# Velotour_2022_V1_0.net
KiCad netlist of a schematic drawn in Altium Designer
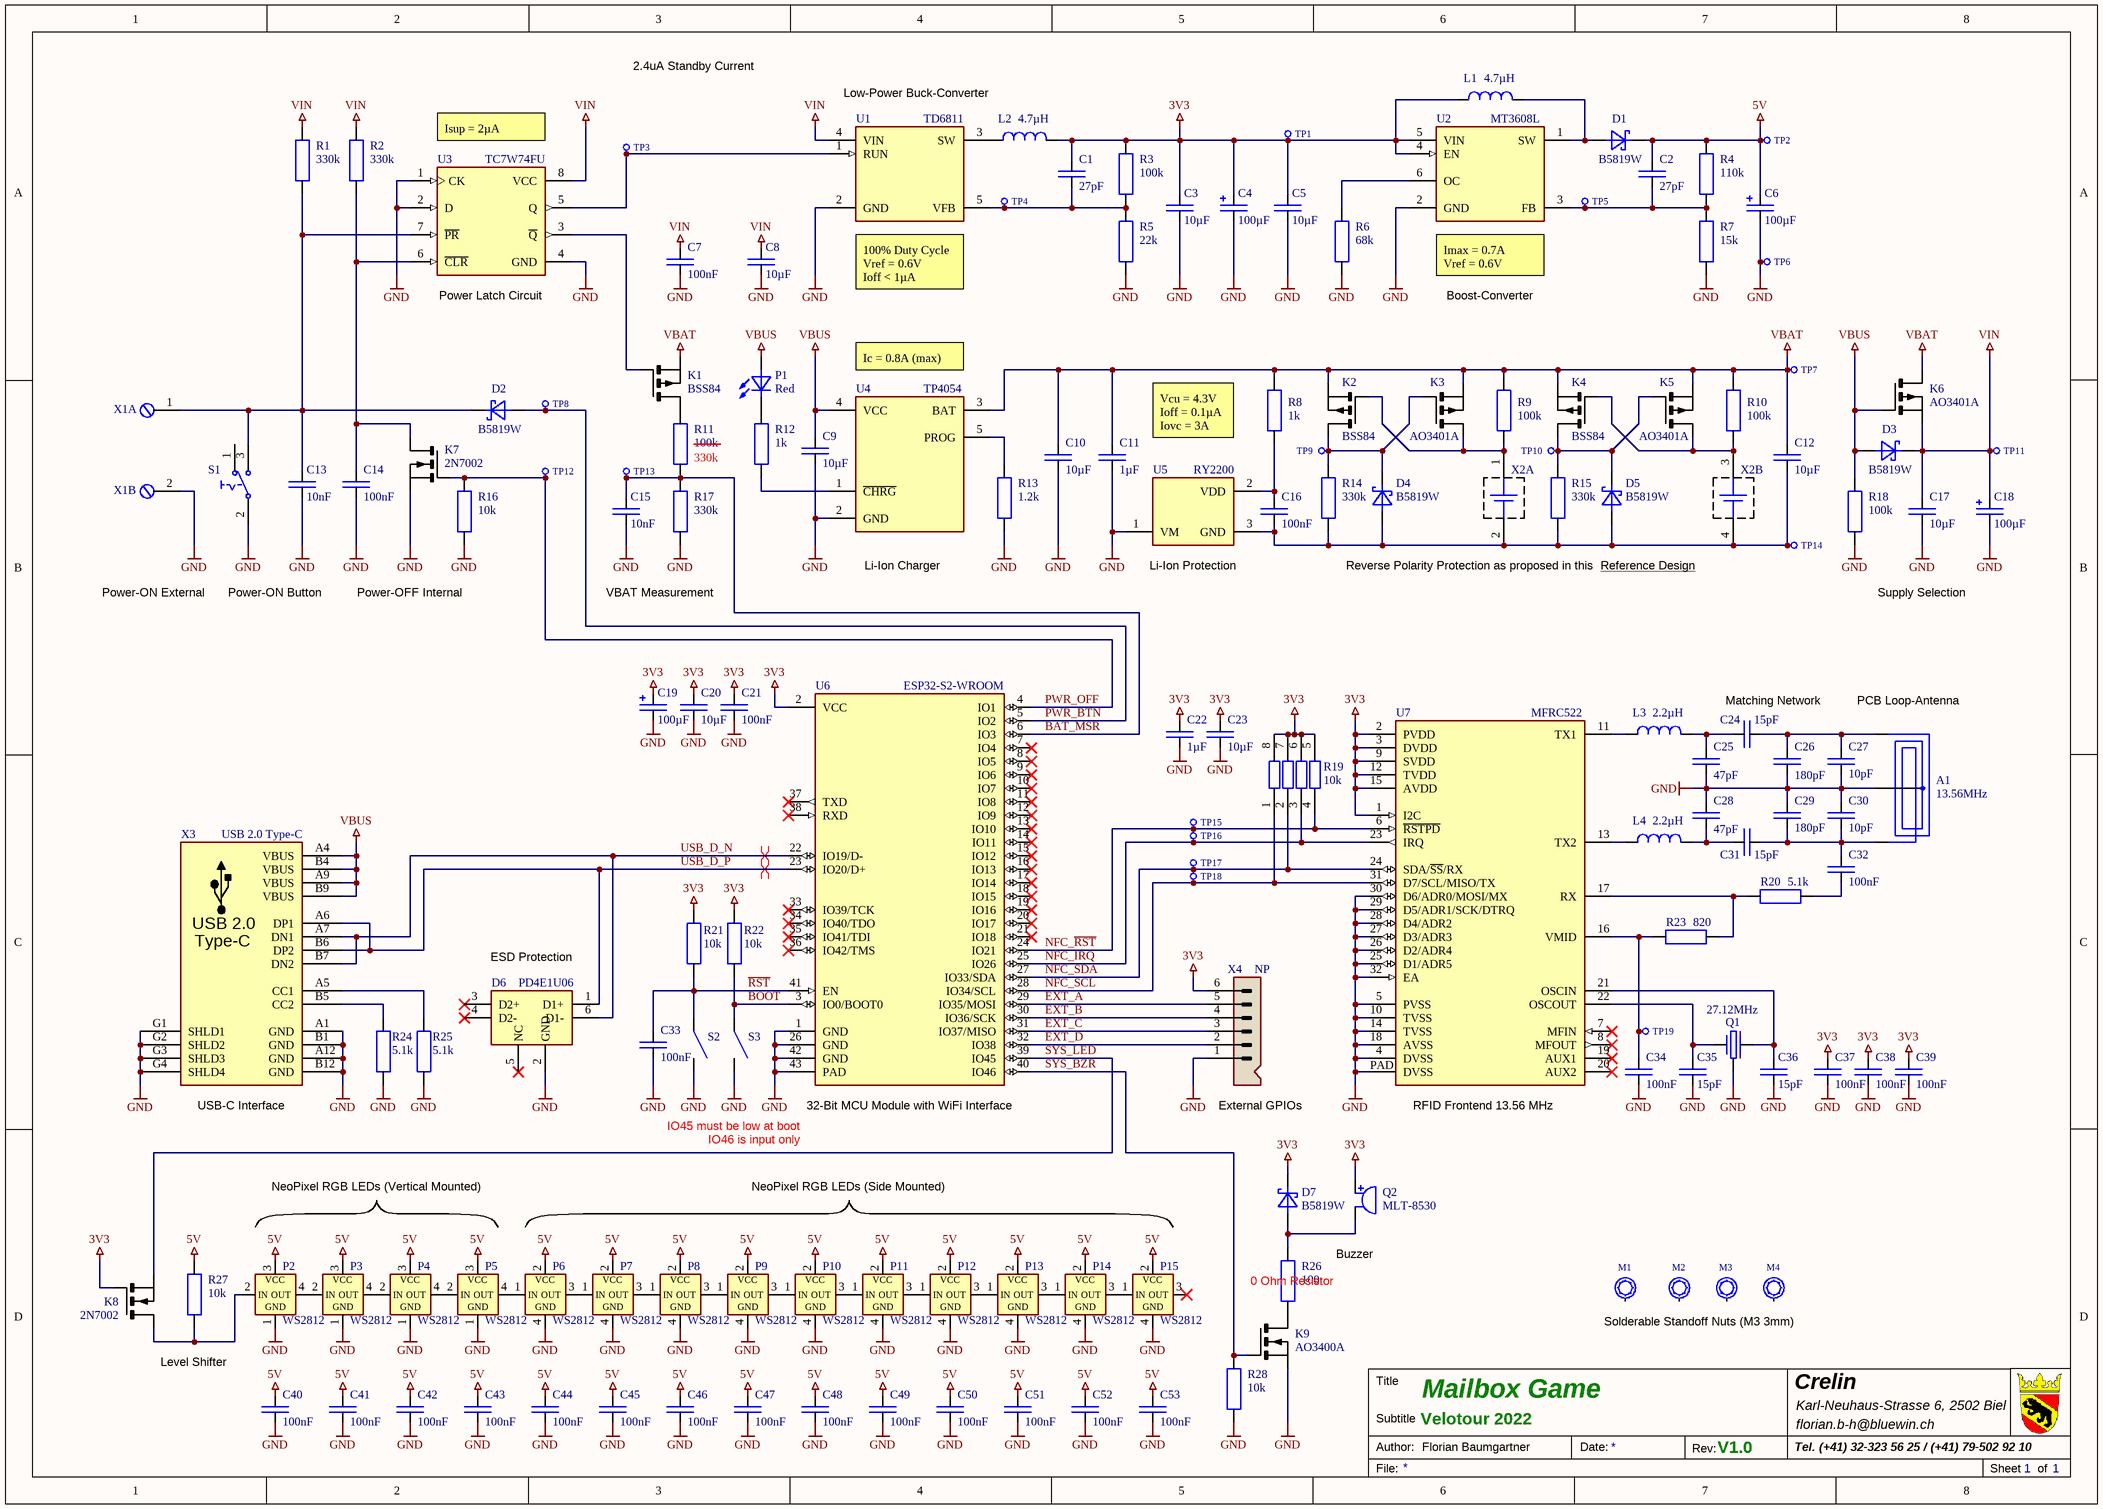
[diagram p0: Velotour_2022_V1.0.SchDoc]

(export (version "E")
  (design (tool "Eeschema 10.0.6"))
  (components
    (comp (ref "A1")
      (value "13.56MHz")
      (footprint "SMD Loop-Antenna 13.56MHz")
      (description "PCB Loop-Antenna")
      (libsource (lib "Velotour_2022") (part "A-Loop-Antenna"))
    )
    (comp (ref "C1")
      (value "27pF")
      (footprint "SMD Keramikkondensator 0603")
      (description "CAP-MK")
      (libsource (lib "AudioAmp") (part "C-CAPACITOR"))
    )
    (comp (ref "C2")
      (value "27pF")
      (footprint "SMD Keramikkondensator 0603")
      (description "CAP-MK")
      (libsource (lib "AudioAmp") (part "C-CAPACITOR"))
    )
    (comp (ref "C3")
      (value "10µF")
      (footprint "SMD Keramikkondensator 1206")
      (description "CAP-MK")
      (libsource (lib "AudioAmp") (part "C-CAPACITOR"))
    )
    (comp (ref "C4")
      (value "100µF")
      (footprint "SMD Tantalkondensator 1210 +")
      (description "CAP-Elko")
      (libsource (lib "TFS Integrated Library") (part "C-ELCAP"))
    )
    (comp (ref "C5")
      (value "10µF")
      (footprint "SMD Keramikkondensator 1206")
      (description "CAP-MK")
      (libsource (lib "AudioAmp") (part "C-CAPACITOR"))
    )
    (comp (ref "C6")
      (value "100µF")
      (footprint "SMD Tantalkondensator 1210 +")
      (description "CAP-Elko")
      (libsource (lib "TFS Integrated Library") (part "C-ELCAP"))
    )
    (comp (ref "C7")
      (value "100nF")
      (footprint "SMD Keramikkondensator 0603")
      (description "SMD Ceramic Capacitor E6")
      (libsource (lib "Ceramic Capacitors-E6") (part "E6 - 100nF"))
    )
    (comp (ref "C8")
      (value "10µF")
      (footprint "SMD Keramikkondensator 1206")
      (description "CAP-MK")
      (libsource (lib "AudioAmp") (part "C-CAPACITOR"))
    )
    (comp (ref "C9")
      (value "10µF")
      (footprint "SMD Keramikkondensator 1206")
      (description "SMD Ceramic Capacitor E6")
      (libsource (lib "Ceramic Capacitors-E6") (part "E6 - 10uF"))
    )
    (comp (ref "C10")
      (value "10µF")
      (footprint "SMD Keramikkondensator 1206")
      (description "SMD Ceramic Capacitor E6")
      (libsource (lib "Ceramic Capacitors-E6") (part "E6 - 10uF"))
    )
    (comp (ref "C11")
      (value "1µF")
      (footprint "SMD Keramikkondensator 0603")
      (description "CAP-MK")
      (libsource (lib "AudioAmp") (part "C-CAPACITOR"))
    )
    (comp (ref "C12")
      (value "10µF")
      (footprint "SMD Keramikkondensator 1206")
      (description "SMD Ceramic Capacitor E6")
      (libsource (lib "Ceramic Capacitors-E6") (part "E6 - 10uF"))
    )
    (comp (ref "C13")
      (value "10nF")
      (footprint "SMD Keramikkondensator 0603")
      (description "CAP-MK")
      (libsource (lib "AudioAmp") (part "C-CAPACITOR"))
    )
    (comp (ref "C14")
      (value "100nF")
      (footprint "SMD Keramikkondensator 0603")
      (description "SMD Ceramic Capacitor E6")
      (libsource (lib "Ceramic Capacitors-E6") (part "E6 - 100nF"))
    )
    (comp (ref "C15")
      (value "10nF")
      (footprint "SMD Keramikkondensator 0603")
      (description "CAP-MK")
      (libsource (lib "AudioAmp") (part "C-CAPACITOR"))
    )
    (comp (ref "C16")
      (value "100nF")
      (footprint "SMD Keramikkondensator 0603")
      (description "SMD Ceramic Capacitor E6")
      (libsource (lib "Ceramic Capacitors-E6") (part "E6 - 100nF"))
    )
    (comp (ref "C17")
      (value "10µF")
      (footprint "SMD Keramikkondensator 1206")
      (description "SMD Ceramic Capacitor E6")
      (libsource (lib "Ceramic Capacitors-E6") (part "E6 - 10uF"))
    )
    (comp (ref "C18")
      (value "100µF")
      (footprint "SMD Tantalkondensator 1210 +")
      (description "CAP-Elko")
      (libsource (lib "TFS Integrated Library") (part "C-ELCAP"))
    )
    (comp (ref "C19")
      (value "100µF")
      (footprint "SMD Tantalkondensator 1210 +")
      (description "CAP-Elko")
      (libsource (lib "TFS Integrated Library") (part "C-ELCAP"))
    )
    (comp (ref "C20")
      (value "10µF")
      (footprint "SMD Keramikkondensator 1206")
      (description "SMD Ceramic Capacitor E6")
      (libsource (lib "Ceramic Capacitors-E6") (part "E6 - 10uF"))
    )
    (comp (ref "C21")
      (value "100nF")
      (footprint "SMD Keramikkondensator 0603")
      (description "SMD Ceramic Capacitor E6")
      (libsource (lib "Ceramic Capacitors-E6") (part "E6 - 100nF"))
    )
    (comp (ref "C22")
      (value "1µF")
      (footprint "SMD Keramikkondensator 0603")
      (description "CAP-MK")
      (libsource (lib "AudioAmp") (part "C-CAPACITOR"))
    )
    (comp (ref "C23")
      (value "10µF")
      (footprint "SMD Keramikkondensator 1206")
      (description "SMD Ceramic Capacitor E6")
      (libsource (lib "Ceramic Capacitors-E6") (part "E6 - 10uF"))
    )
    (comp (ref "C24")
      (value "15pF")
      (footprint "SMD Keramikkondensator 0603")
      (description "CAP-MK")
      (libsource (lib "AudioAmp") (part "C-CAPACITOR"))
    )
    (comp (ref "C25")
      (value "47pF")
      (footprint "SMD Keramikkondensator 0603")
      (description "CAP-MK")
      (libsource (lib "AudioAmp") (part "C-CAPACITOR"))
    )
    (comp (ref "C26")
      (value "180pF")
      (footprint "SMD Keramikkondensator 0603")
      (description "CAP-MK")
      (libsource (lib "AudioAmp") (part "C-CAPACITOR"))
    )
    (comp (ref "C27")
      (value "10pF")
      (footprint "SMD Keramikkondensator 0603")
      (description "CAP-MK")
      (libsource (lib "AudioAmp") (part "C-CAPACITOR"))
    )
    (comp (ref "C28")
      (value "47pF")
      (footprint "SMD Keramikkondensator 0603")
      (description "CAP-MK")
      (libsource (lib "AudioAmp") (part "C-CAPACITOR"))
    )
    (comp (ref "C29")
      (value "180pF")
      (footprint "SMD Keramikkondensator 0603")
      (description "CAP-MK")
      (libsource (lib "AudioAmp") (part "C-CAPACITOR"))
    )
    (comp (ref "C30")
      (value "10pF")
      (footprint "SMD Keramikkondensator 0603")
      (description "CAP-MK")
      (libsource (lib "AudioAmp") (part "C-CAPACITOR"))
    )
    (comp (ref "C31")
      (value "15pF")
      (footprint "SMD Keramikkondensator 0603")
      (description "CAP-MK")
      (libsource (lib "AudioAmp") (part "C-CAPACITOR"))
    )
    (comp (ref "C32")
      (value "100nF")
      (footprint "SMD Keramikkondensator 0603")
      (description "SMD Ceramic Capacitor E6")
      (libsource (lib "Ceramic Capacitors-E6") (part "E6 - 100nF"))
    )
    (comp (ref "C33")
      (value "100nF")
      (footprint "SMD Keramikkondensator 0603")
      (description "SMD Ceramic Capacitor E6")
      (libsource (lib "Ceramic Capacitors-E6") (part "E6 - 100nF"))
    )
    (comp (ref "C34")
      (value "100nF")
      (footprint "SMD Keramikkondensator 0603")
      (description "SMD Ceramic Capacitor E6")
      (libsource (lib "Ceramic Capacitors-E6") (part "E6 - 100nF"))
    )
    (comp (ref "C35")
      (value "15pF")
      (footprint "SMD Keramikkondensator 0603")
      (description "CAP-MK")
      (libsource (lib "AudioAmp") (part "C-CAPACITOR"))
    )
    (comp (ref "C36")
      (value "15pF")
      (footprint "SMD Keramikkondensator 0603")
      (description "CAP-MK")
      (libsource (lib "AudioAmp") (part "C-CAPACITOR"))
    )
    (comp (ref "C37")
      (value "100nF")
      (footprint "SMD Keramikkondensator 0603")
      (description "SMD Ceramic Capacitor E6")
      (libsource (lib "Ceramic Capacitors-E6") (part "E6 - 100nF"))
    )
    (comp (ref "C38")
      (value "100nF")
      (footprint "SMD Keramikkondensator 0603")
      (description "SMD Ceramic Capacitor E6")
      (libsource (lib "Ceramic Capacitors-E6") (part "E6 - 100nF"))
    )
    (comp (ref "C39")
      (value "100nF")
      (footprint "SMD Keramikkondensator 0603")
      (description "SMD Ceramic Capacitor E6")
      (libsource (lib "Ceramic Capacitors-E6") (part "E6 - 100nF"))
    )
    (comp (ref "C40")
      (value "100nF")
      (footprint "SMD Keramikkondensator 0603")
      (description "SMD Ceramic Capacitor E6")
      (libsource (lib "Ceramic Capacitors-E6") (part "E6 - 100nF"))
    )
    (comp (ref "C41")
      (value "100nF")
      (footprint "SMD Keramikkondensator 0603")
      (description "SMD Ceramic Capacitor E6")
      (libsource (lib "Ceramic Capacitors-E6") (part "E6 - 100nF"))
    )
    (comp (ref "C42")
      (value "100nF")
      (footprint "SMD Keramikkondensator 0603")
      (description "SMD Ceramic Capacitor E6")
      (libsource (lib "Ceramic Capacitors-E6") (part "E6 - 100nF"))
    )
    (comp (ref "C43")
      (value "100nF")
      (footprint "SMD Keramikkondensator 0603")
      (description "SMD Ceramic Capacitor E6")
      (libsource (lib "Ceramic Capacitors-E6") (part "E6 - 100nF"))
    )
    (comp (ref "C44")
      (value "100nF")
      (footprint "SMD Keramikkondensator 0603")
      (description "SMD Ceramic Capacitor E6")
      (libsource (lib "Ceramic Capacitors-E6") (part "E6 - 100nF"))
    )
    (comp (ref "C45")
      (value "100nF")
      (footprint "SMD Keramikkondensator 0603")
      (description "SMD Ceramic Capacitor E6")
      (libsource (lib "Ceramic Capacitors-E6") (part "E6 - 100nF"))
    )
    (comp (ref "C46")
      (value "100nF")
      (footprint "SMD Keramikkondensator 0603")
      (description "SMD Ceramic Capacitor E6")
      (libsource (lib "Ceramic Capacitors-E6") (part "E6 - 100nF"))
    )
    (comp (ref "C47")
      (value "100nF")
      (footprint "SMD Keramikkondensator 0603")
      (description "SMD Ceramic Capacitor E6")
      (libsource (lib "Ceramic Capacitors-E6") (part "E6 - 100nF"))
    )
    (comp (ref "C48")
      (value "100nF")
      (footprint "SMD Keramikkondensator 0603")
      (description "SMD Ceramic Capacitor E6")
      (libsource (lib "Ceramic Capacitors-E6") (part "E6 - 100nF"))
    )
    (comp (ref "C49")
      (value "100nF")
      (footprint "SMD Keramikkondensator 0603")
      (description "SMD Ceramic Capacitor E6")
      (libsource (lib "Ceramic Capacitors-E6") (part "E6 - 100nF"))
    )
    (comp (ref "C50")
      (value "100nF")
      (footprint "SMD Keramikkondensator 0603")
      (description "SMD Ceramic Capacitor E6")
      (libsource (lib "Ceramic Capacitors-E6") (part "E6 - 100nF"))
    )
    (comp (ref "C51")
      (value "100nF")
      (footprint "SMD Keramikkondensator 0603")
      (description "SMD Ceramic Capacitor E6")
      (libsource (lib "Ceramic Capacitors-E6") (part "E6 - 100nF"))
    )
    (comp (ref "C52")
      (value "100nF")
      (footprint "SMD Keramikkondensator 0603")
      (description "SMD Ceramic Capacitor E6")
      (libsource (lib "Ceramic Capacitors-E6") (part "E6 - 100nF"))
    )
    (comp (ref "C53")
      (value "100nF")
      (footprint "SMD Keramikkondensator 0603")
      (description "SMD Ceramic Capacitor E6")
      (libsource (lib "Ceramic Capacitors-E6") (part "E6 - 100nF"))
    )
    (comp (ref "D1")
      (value "B5819W")
      (footprint "SMD Diode SOD-123")
      (description "S-DIODE")
      (libsource (lib "TFS Integrated Library") (part "R-DIODE{colon}SCHKY"))
    )
    (comp (ref "D2")
      (value "B5819W")
      (footprint "SMD Diode SOD-123")
      (description "S-DIODE")
      (libsource (lib "TFS Integrated Library") (part "R-DIODE{colon}SCHKY"))
    )
    (comp (ref "D3")
      (value "B5819W")
      (footprint "SMD Diode SOD-123")
      (description "S-DIODE")
      (libsource (lib "TFS Integrated Library") (part "R-DIODE{colon}SCHKY"))
    )
    (comp (ref "D4")
      (value "B5819W")
      (footprint "SMD Diode SOD-123")
      (description "S-DIODE")
      (libsource (lib "TFS Integrated Library") (part "R-DIODE{colon}SCHKY"))
    )
    (comp (ref "D5")
      (value "B5819W")
      (footprint "SMD Diode SOD-123")
      (description "S-DIODE")
      (libsource (lib "TFS Integrated Library") (part "R-DIODE{colon}SCHKY"))
    )
    (comp (ref "D6")
      (value "PD4E1U06")
      (footprint "SMD IC SOT-363 (SC-70-6)")
      (description "Unidirectional 3A (8/20us) 15V (Typ) 6.5V 5.5V (Max) SOT-363 ESD Protection Devices ROHS")
      (libsource (lib "Fleet-Monitor") (part "PD4E1U06DCKR"))
    )
    (comp (ref "D7")
      (value "B5819W")
      (footprint "SMD Diode SOD-123")
      (description "S-DIODE")
      (libsource (lib "TFS Integrated Library") (part "R-DIODE{colon}SCHKY"))
    )
    (comp (ref "K1")
      (value "BSS84")
      (footprint "SMD MOSFET SOT-23")
      (description "MOSFET P-Channel")
      (libsource (lib "VLD-Monitor_V1.0") (part "K-FET{colon}PIGE"))
    )
    (comp (ref "K2")
      (value "BSS84")
      (footprint "SMD MOSFET SOT-23")
      (description "MOSFET P-Channel")
      (libsource (lib "") (part "K-FET{colon}PIGE_2"))
    )
    (comp (ref "K3")
      (value "AO3401A")
      (footprint "SMD MOSFET SOT-23")
      (description "MOSFET P-Channel")
      (libsource (lib "VLD-Monitor_V1.0") (part "K-FET{colon}PIGE"))
    )
    (comp (ref "K4")
      (value "BSS84")
      (footprint "SMD MOSFET SOT-23")
      (description "MOSFET P-Channel")
      (libsource (lib "") (part "K-FET{colon}PIGE_2"))
    )
    (comp (ref "K5")
      (value "AO3401A")
      (footprint "SMD MOSFET SOT-23")
      (description "MOSFET P-Channel")
      (libsource (lib "VLD-Monitor_V1.0") (part "K-FET{colon}PIGE"))
    )
    (comp (ref "K6")
      (value "AO3401A")
      (footprint "SMD MOSFET SOT-23")
      (description "MOSFET P-Channel")
      (libsource (lib "") (part "K-FET{colon}PIGE_1"))
    )
    (comp (ref "K7")
      (value "2N7002")
      (footprint "SMD MOSFET SOT-23")
      (description "MOSFET N-Channel")
      (libsource (lib "") (part "K-FET{colon}NIGE_2"))
    )
    (comp (ref "K8")
      (value "2N7002")
      (footprint "SMD MOSFET SOT-23")
      (description "MOSFET N-Channel")
      (libsource (lib "Nixie-Test") (part "K-FET{colon}NIGE"))
    )
    (comp (ref "K9")
      (value "AO3400A")
      (footprint "SMD MOSFET SOT-23")
      (description "MOSFET N-Channel")
      (libsource (lib "") (part "K-FET{colon}NIGE_1"))
    )
    (comp (ref "L1")
      (value "4.7µH")
      (footprint "SMD Inductor 3.2x2.5x1.7")
      (description "Shielded Power Inductor")
      (libsource (lib "Nixie-Test") (part "L-COIL"))
    )
    (comp (ref "L2")
      (value "4.7µH")
      (footprint "SMD Inductor 3.2x2.5x1.7")
      (description "Shielded Power Inductor")
      (libsource (lib "Nixie-Test") (part "L-COIL"))
    )
    (comp (ref "L3")
      (value "2.2µH")
      (footprint "SMD Inductor 0805")
      (description "Multilayer Chip Inductor")
      (libsource (lib "Nixie-Test") (part "L-COIL"))
    )
    (comp (ref "L4")
      (value "2.2µH")
      (footprint "SMD Inductor 0805")
      (description "Multilayer Chip Inductor")
      (libsource (lib "Nixie-Test") (part "L-COIL"))
    )
    (comp (ref "M1")
      (value "SMTSO-M3-3ET")
      (footprint "SMD Solder-Nut (M3 3mm)")
      (description "Solderable Standoff Nut")
      (libsource (lib "Velotour_2022") (part "M-Spacer_M3_3mm"))
    )
    (comp (ref "M2")
      (value "SMTSO-M3-3ET")
      (footprint "SMD Solder-Nut (M3 3mm)")
      (description "Solderable Standoff Nut")
      (libsource (lib "Velotour_2022") (part "M-Spacer_M3_3mm"))
    )
    (comp (ref "M3")
      (value "SMTSO-M3-3ET")
      (footprint "SMD Solder-Nut (M3 3mm)")
      (description "Solderable Standoff Nut")
      (libsource (lib "Velotour_2022") (part "M-Spacer_M3_3mm"))
    )
    (comp (ref "M4")
      (value "SMTSO-M3-3ET")
      (footprint "SMD Solder-Nut (M3 3mm)")
      (description "Solderable Standoff Nut")
      (libsource (lib "Velotour_2022") (part "M-Spacer_M3_3mm"))
    )
    (comp (ref "P1")
      (value "Red")
      (footprint "SMD LED 0603")
      (description "LED (als Lampe E / alt H)")
      (libsource (lib "TFS Integrated Library") (part "P-LED"))
    )
    (comp (ref "P2")
      (value "WS2812")
      (footprint "SMD LED WS2812B-3528")
      (description "Smart RGB-LED")
      (libsource (lib "Velotour_2022") (part "P-WS2812B-3528"))
    )
    (comp (ref "P3")
      (value "WS2812")
      (footprint "SMD LED WS2812B-3528")
      (description "Smart RGB-LED")
      (libsource (lib "Velotour_2022") (part "P-WS2812B-3528"))
    )
    (comp (ref "P4")
      (value "WS2812")
      (footprint "SMD LED WS2812B-3528")
      (description "Smart RGB-LED")
      (libsource (lib "Velotour_2022") (part "P-WS2812B-3528"))
    )
    (comp (ref "P5")
      (value "WS2812")
      (footprint "SMD LED WS2812B-3528")
      (description "Smart RGB-LED")
      (libsource (lib "Velotour_2022") (part "P-WS2812B-3528"))
    )
    (comp (ref "P6")
      (value "WS2812")
      (footprint "SMD LED WS2812B-4020")
      (description "Smart RGB-LED")
      (libsource (lib "Velotour_2022") (part "P-WS2812B-4020"))
    )
    (comp (ref "P7")
      (value "WS2812")
      (footprint "SMD LED WS2812B-4020")
      (description "Smart RGB-LED")
      (libsource (lib "Velotour_2022") (part "P-WS2812B-4020"))
    )
    (comp (ref "P8")
      (value "WS2812")
      (footprint "SMD LED WS2812B-4020")
      (description "Smart RGB-LED")
      (libsource (lib "Velotour_2022") (part "P-WS2812B-4020"))
    )
    (comp (ref "P9")
      (value "WS2812")
      (footprint "SMD LED WS2812B-4020")
      (description "Smart RGB-LED")
      (libsource (lib "Velotour_2022") (part "P-WS2812B-4020"))
    )
    (comp (ref "P10")
      (value "WS2812")
      (footprint "SMD LED WS2812B-4020")
      (description "Smart RGB-LED")
      (libsource (lib "Velotour_2022") (part "P-WS2812B-4020"))
    )
    (comp (ref "P11")
      (value "WS2812")
      (footprint "SMD LED WS2812B-4020")
      (description "Smart RGB-LED")
      (libsource (lib "Velotour_2022") (part "P-WS2812B-4020"))
    )
    (comp (ref "P12")
      (value "WS2812")
      (footprint "SMD LED WS2812B-4020")
      (description "Smart RGB-LED")
      (libsource (lib "Velotour_2022") (part "P-WS2812B-4020"))
    )
    (comp (ref "P13")
      (value "WS2812")
      (footprint "SMD LED WS2812B-4020")
      (description "Smart RGB-LED")
      (libsource (lib "Velotour_2022") (part "P-WS2812B-4020"))
    )
    (comp (ref "P14")
      (value "WS2812")
      (footprint "SMD LED WS2812B-4020")
      (description "Smart RGB-LED")
      (libsource (lib "Velotour_2022") (part "P-WS2812B-4020"))
    )
    (comp (ref "P15")
      (value "WS2812")
      (footprint "SMD LED WS2812B-4020")
      (description "Smart RGB-LED")
      (libsource (lib "Velotour_2022") (part "P-WS2812B-4020"))
    )
    (comp (ref "Q1")
      (value "27.12MHz")
      (footprint "SMD Crystal 3.2X2.5X0.8")
      (libsource (lib "LED-Ring") (part "B-QUARZ-CAP"))
    )
    (comp (ref "Q2")
      (value "MLT-8530")
      (footprint "SMD Buzzer (MLT-8530)")
      (description "Electromagnetic Buzzer")
      (libsource (lib "Velotour_2022") (part "Q-Buzzer"))
    )
    (comp (ref "R1")
      (value "330k")
      (footprint "SMD Widerstand 0603")
      (description "RES (E=Heizwiderstand B=Messwandler)")
      (libsource (lib "") (part "R-RESISTOR_2"))
    )
    (comp (ref "R2")
      (value "330k")
      (footprint "SMD Widerstand 0603")
      (description "RES (E=Heizwiderstand B=Messwandler)")
      (libsource (lib "") (part "R-RESISTOR_2"))
    )
    (comp (ref "R3")
      (value "100k")
      (footprint "SMD Widerstand 0603")
      (description "RES (E=Heizwiderstand B=Messwandler)")
      (libsource (lib "") (part "R-RESISTOR_2"))
    )
    (comp (ref "R4")
      (value "110k")
      (footprint "SMD Widerstand 0603")
      (description "RES (E=Heizwiderstand B=Messwandler)")
      (libsource (lib "") (part "R-RESISTOR_2"))
    )
    (comp (ref "R5")
      (value "22k")
      (footprint "SMD Widerstand 0603")
      (description "RES (E=Heizwiderstand B=Messwandler)")
      (libsource (lib "TFS Integrated Library") (part "R-RESISTOR"))
    )
    (comp (ref "R6")
      (value "68k")
      (footprint "SMD Widerstand 0603")
      (description "RES (E=Heizwiderstand B=Messwandler)")
      (libsource (lib "") (part "R-RESISTOR_1"))
    )
    (comp (ref "R7")
      (value "15k")
      (footprint "SMD Widerstand 0603")
      (description "RES (E=Heizwiderstand B=Messwandler)")
      (libsource (lib "") (part "R-RESISTOR_2"))
    )
    (comp (ref "R8")
      (value "1k")
      (footprint "SMD Widerstand 0603")
      (description "RES (E=Heizwiderstand B=Messwandler)")
      (libsource (lib "TFS Integrated Library") (part "R-RESISTOR"))
    )
    (comp (ref "R9")
      (value "100k")
      (footprint "SMD Widerstand 0603")
      (description "RES (E=Heizwiderstand B=Messwandler)")
      (libsource (lib "") (part "R-RESISTOR_2"))
    )
    (comp (ref "R10")
      (value "100k")
      (footprint "SMD Widerstand 0603")
      (description "RES (E=Heizwiderstand B=Messwandler)")
      (libsource (lib "") (part "R-RESISTOR_2"))
    )
    (comp (ref "R11")
      (value "100k")
      (footprint "SMD Widerstand 0603")
      (description "RES (E=Heizwiderstand B=Messwandler)")
      (libsource (lib "") (part "R-RESISTOR_2"))
    )
    (comp (ref "R12")
      (value "1k")
      (footprint "SMD Widerstand 0603")
      (description "RES (E=Heizwiderstand B=Messwandler)")
      (libsource (lib "") (part "R-RESISTOR_3"))
    )
    (comp (ref "R13")
      (value "1.2k")
      (footprint "SMD Widerstand 0603")
      (description "RES (E=Heizwiderstand B=Messwandler)")
      (libsource (lib "") (part "R-RESISTOR_2"))
    )
    (comp (ref "R14")
      (value "330k")
      (footprint "SMD Widerstand 0603")
      (description "RES (E=Heizwiderstand B=Messwandler)")
      (libsource (lib "") (part "R-RESISTOR_2"))
    )
    (comp (ref "R15")
      (value "330k")
      (footprint "SMD Widerstand 0603")
      (description "RES (E=Heizwiderstand B=Messwandler)")
      (libsource (lib "") (part "R-RESISTOR_2"))
    )
    (comp (ref "R16")
      (value "10k")
      (footprint "SMD Widerstand 0603")
      (description "RES (E=Heizwiderstand B=Messwandler)")
      (libsource (lib "TFS Integrated Library") (part "R-RESISTOR"))
    )
    (comp (ref "R17")
      (value "330k")
      (footprint "SMD Widerstand 0603")
      (description "RES (E=Heizwiderstand B=Messwandler)")
      (libsource (lib "") (part "R-RESISTOR_2"))
    )
    (comp (ref "R18")
      (value "100k")
      (footprint "SMD Widerstand 0603")
      (description "RES (E=Heizwiderstand B=Messwandler)")
      (libsource (lib "") (part "R-RESISTOR_2"))
    )
    (comp (ref "R19")
      (value "10k")
      (footprint "SMD Widerstand Array 4-Fach 0603")
      (description "Isolated Resistor Array")
      (libsource (lib "Fleet-Monitor") (part "R-Array Single Quad E24 - 10k"))
    )
    (comp (ref "R20")
      (value "5.1k")
      (footprint "SMD Widerstand 0603")
      (description "RES (E=Heizwiderstand B=Messwandler)")
      (libsource (lib "") (part "R-RESISTOR_2"))
    )
    (comp (ref "R21")
      (value "10k")
      (footprint "SMD Widerstand 0603")
      (description "RES (E=Heizwiderstand B=Messwandler)")
      (libsource (lib "TFS Integrated Library") (part "R-RESISTOR"))
    )
    (comp (ref "R22")
      (value "10k")
      (footprint "SMD Widerstand 0603")
      (description "RES (E=Heizwiderstand B=Messwandler)")
      (libsource (lib "TFS Integrated Library") (part "R-RESISTOR"))
    )
    (comp (ref "R23")
      (value "820")
      (footprint "SMD Widerstand 0603")
      (description "SMD-Widerstand 1/4W")
      (libsource (lib "Backplane_1") (part "R-RESISTOR"))
    )
    (comp (ref "R24")
      (value "5.1k")
      (footprint "SMD Widerstand 0603")
      (description "RES (E=Heizwiderstand B=Messwandler)")
      (libsource (lib "") (part "R-RESISTOR_1"))
    )
    (comp (ref "R25")
      (value "5.1k")
      (footprint "SMD Widerstand 0603")
      (description "RES (E=Heizwiderstand B=Messwandler)")
      (libsource (lib "") (part "R-RESISTOR_1"))
    )
    (comp (ref "R26")
      (value "100")
      (footprint "SMD Widerstand 0603")
      (description "SMD-Widerstand 1/4W")
      (libsource (lib "") (part "R-RESISTOR_1"))
    )
    (comp (ref "R27")
      (value "10k")
      (footprint "SMD Widerstand 0603")
      (description "RES (E=Heizwiderstand B=Messwandler)")
      (libsource (lib "TFS Integrated Library") (part "R-RESISTOR"))
    )
    (comp (ref "R28")
      (value "10k")
      (footprint "SMD Widerstand 0603")
      (description "RES (E=Heizwiderstand B=Messwandler)")
      (libsource (lib "TFS Integrated Library") (part "R-RESISTOR"))
    )
    (comp (ref "S1")
      (value "SS075Q102F035V2A")
      (footprint "THT Micro Switch (SS075Q102F035V2A)")
      (description "Micro Detector Switch")
      (libsource (lib "Custom ST-Link") (part "S-PCM12SMTR"))
    )
    (comp (ref "S2")
      (value "SMD-Button")
      (footprint "SMD Button 5.2x5.2")
      (description "Button SPST")
      (libsource (lib "Switches") (part "Button 3mmx2.5mm"))
    )
    (comp (ref "S3")
      (value "SMD-Button")
      (footprint "SMD Button 5.2x5.2")
      (description "Button SPST")
      (libsource (lib "Switches") (part "Button 3mmx2.5mm"))
    )
    (comp (ref "TP1")
      (value "X-TP")
      (footprint "SMD Testpunkt Ø1mm")
      (description "Testpunkt")
      (libsource (lib "VLD-Monitor_V1.0") (part "X-TP"))
    )
    (comp (ref "TP2")
      (value "X-TP")
      (footprint "SMD Testpunkt Ø1mm")
      (description "Testpunkt")
      (libsource (lib "VLD-Monitor_V1.0") (part "X-TP"))
    )
    (comp (ref "TP3")
      (value "X-TP")
      (footprint "SMD Testpunkt Ø1mm")
      (description "Testpunkt")
      (libsource (lib "VLD-Monitor_V1.0") (part "X-TP"))
    )
    (comp (ref "TP4")
      (value "X-TP")
      (footprint "SMD Testpunkt Ø1mm")
      (description "Testpunkt")
      (libsource (lib "VLD-Monitor_V1.0") (part "X-TP"))
    )
    (comp (ref "TP5")
      (value "X-TP")
      (footprint "SMD Testpunkt Ø1mm")
      (description "Testpunkt")
      (libsource (lib "VLD-Monitor_V1.0") (part "X-TP"))
    )
    (comp (ref "TP6")
      (value "X-TP")
      (footprint "SMD Testpunkt Ø1mm")
      (description "Testpunkt")
      (libsource (lib "VLD-Monitor_V1.0") (part "X-TP"))
    )
    (comp (ref "TP7")
      (value "X-TP")
      (footprint "SMD Testpunkt Ø1mm")
      (description "Testpunkt")
      (libsource (lib "VLD-Monitor_V1.0") (part "X-TP"))
    )
    (comp (ref "TP8")
      (value "X-TP")
      (footprint "SMD Testpunkt Ø1mm")
      (description "Testpunkt")
      (libsource (lib "VLD-Monitor_V1.0") (part "X-TP"))
    )
    (comp (ref "TP9")
      (value "X-TP")
      (footprint "SMD Testpunkt Ø1mm")
      (description "Testpunkt")
      (libsource (lib "VLD-Monitor_V1.0") (part "X-TP"))
    )
    (comp (ref "TP10")
      (value "X-TP")
      (footprint "SMD Testpunkt Ø1mm")
      (description "Testpunkt")
      (libsource (lib "VLD-Monitor_V1.0") (part "X-TP"))
    )
    (comp (ref "TP11")
      (value "X-TP")
      (footprint "SMD Testpunkt Ø1mm")
      (description "Testpunkt")
      (libsource (lib "VLD-Monitor_V1.0") (part "X-TP"))
    )
    (comp (ref "TP12")
      (value "X-TP")
      (footprint "SMD Testpunkt Ø1mm")
      (description "Testpunkt")
      (libsource (lib "VLD-Monitor_V1.0") (part "X-TP"))
    )
    (comp (ref "TP13")
      (value "X-TP")
      (footprint "SMD Testpunkt Ø1mm")
      (description "Testpunkt")
      (libsource (lib "VLD-Monitor_V1.0") (part "X-TP"))
    )
    (comp (ref "TP14")
      (value "X-TP")
      (footprint "SMD Testpunkt Ø1mm")
      (description "Testpunkt")
      (libsource (lib "VLD-Monitor_V1.0") (part "X-TP"))
    )
    (comp (ref "TP15")
      (value "X-TP")
      (footprint "SMD Testpunkt Ø1mm")
      (description "Testpunkt")
      (libsource (lib "VLD-Monitor_V1.0") (part "X-TP"))
    )
    (comp (ref "TP16")
      (value "X-TP")
      (footprint "SMD Testpunkt Ø1mm")
      (description "Testpunkt")
      (libsource (lib "VLD-Monitor_V1.0") (part "X-TP"))
    )
    (comp (ref "TP17")
      (value "X-TP")
      (footprint "SMD Testpunkt Ø1mm")
      (description "Testpunkt")
      (libsource (lib "VLD-Monitor_V1.0") (part "X-TP"))
    )
    (comp (ref "TP18")
      (value "X-TP")
      (footprint "SMD Testpunkt Ø1mm")
      (description "Testpunkt")
      (libsource (lib "VLD-Monitor_V1.0") (part "X-TP"))
    )
    (comp (ref "TP19")
      (value "X-TP")
      (footprint "SMD Testpunkt Ø1mm")
      (description "Testpunkt")
      (libsource (lib "VLD-Monitor_V1.0") (part "X-TP"))
    )
    (comp (ref "U1")
      (value "TD6811")
      (footprint "SMD IC SOT-23-5")
      (description "1.5MHz 1.2A Synchronous Step-Down Converter")
      (libsource (lib "Velotour_2022") (part "U-TD6811"))
    )
    (comp (ref "U2")
      (value "MT3608L")
      (footprint "SMD IC SOT-23-6")
      (description "1.2MHz 2.5A Current Mode Step-Up Converter")
      (libsource (lib "Velotour_2022") (part "U-MT3608L"))
    )
    (comp (ref "U3")
      (value "TC7W74FU")
      (footprint "SMD IC TSSOP-8")
      (description "Low-Power D-Flip-Flop with Preset & Clear")
      (libsource (lib "Velotour_2022") (part "U-TC7W74FU"))
    )
    (comp (ref "U4")
      (value "TP4054")
      (footprint "SMD IC SOT-23-5")
      (description "Standalone Linear Li-Ion Battery Charger")
      (libsource (lib "Velotour_2022") (part "U-TP4054"))
    )
    (comp (ref "U5")
      (value "RY2200")
      (footprint "SMD IC SOT-23-3")
      (description "One Cell Li-ion and Li-poly Battery Protection IC")
      (libsource (lib "Velotour_2022") (part "U-RY2200"))
    )
    (comp (ref "U6")
      (value "ESP32-S2-WROOM")
      (footprint "SMD ESP32-S2-WROOM")
      (description "WiFi 802.11b/g/n Transceiver Module 2.4GHz Antenna, I-PEX Surface Mount")
      (libsource (lib "Fleet-Monitor") (part "ESP32-S2-WROOM"))
    )
    (comp (ref "U7")
      (value "MFRC522")
      (footprint "SMD IC QFN-32")
      (description "Standard performance MIFARE and NTAG frontend")
      (libsource (lib "Velotour_2022") (part "U-MFRC522"))
    )
    (comp (ref "X1")
      (value "X-Klemme (2-Pol)")
      (footprint "THT Schraubklemme 2-Pol (WJ500V-5.08-2P)")
      (libsource (lib "Quad-Current-Probe") (part "X-Klemme (2-Pol)"))
    )
    (comp (ref "X2")
      (value "18650 Dual Battery Holder")
      (footprint "SMD Battery-Holder (1048P)")
      (libsource (lib "Velotour_2022") (part "X-18650_Dual-Holder"))
    )
    (comp (ref "X3")
      (value "USB 2.0 Type-C")
      (footprint "THT USB-C Socket (KH-TYPE-C-L10-14P)")
      (description "Type-C")
      (libsource (lib "Velotour_2022") (part "X-USB-Buchse_Vertical"))
    )
    (comp (ref "X4")
      (value "NP")
      (footprint "THT Pin-Header 1x6 (NP)")
      (libsource (lib "Audio-Beamformer") (part "X-Stiftleiste (6-Fach)"))
    )
  )
  (nets
    (net (code "1") (name "/BAT_MSR") (class "Default")
      (node (ref "C15") (pin "2") (pinfunction "2_2") (pintype "passive"))
      (node (ref "R11") (pin "1") (pinfunction "1_1") (pintype "passive"))
      (node (ref "R17") (pin "2") (pinfunction "2_2") (pintype "passive"))
      (node (ref "TP13") (pin "1") (pinfunction "1_1") (pintype "passive"))
      (node (ref "U6") (pin "6") (pinfunction "IO3_6") (pintype "bidirectional"))
    )
    (net (code "2") (name "/BOOT") (class "Default")
      (node (ref "R22") (pin "1") (pinfunction "1_1") (pintype "passive"))
      (node (ref "S3") (pin "1") (pinfunction "1_1") (pintype "passive"))
      (node (ref "U6") (pin "3") (pinfunction "IO0/BOOT0_3") (pintype "bidirectional"))
    )
    (net (code "3") (name "/EXT_A") (class "Default")
      (node (ref "U6") (pin "29") (pinfunction "IO35/MOSI_29") (pintype "bidirectional"))
      (node (ref "X4") (pin "5") (pinfunction "5_5") (pintype "passive"))
    )
    (net (code "4") (name "/EXT_B") (class "Default")
      (node (ref "U6") (pin "30") (pinfunction "IO36/SCK_30") (pintype "bidirectional"))
      (node (ref "X4") (pin "4") (pinfunction "4_4") (pintype "passive"))
    )
    (net (code "5") (name "/EXT_C") (class "Default")
      (node (ref "U6") (pin "31") (pinfunction "IO37/MISO_31") (pintype "bidirectional"))
      (node (ref "X4") (pin "3") (pinfunction "3_3") (pintype "passive"))
    )
    (net (code "6") (name "/EXT_D") (class "Default")
      (node (ref "U6") (pin "32") (pinfunction "IO38_32") (pintype "bidirectional"))
      (node (ref "X4") (pin "2") (pinfunction "2_2") (pintype "passive"))
    )
    (net (code "7") (name "/NFC_SCL") (class "Default")
      (node (ref "R19") (pin "1") (pinfunction "1_1") (pintype "passive"))
      (node (ref "TP18") (pin "1") (pinfunction "1_1") (pintype "passive"))
      (node (ref "U6") (pin "28") (pinfunction "IO34/SCL_28") (pintype "bidirectional"))
      (node (ref "U7") (pin "31") (pinfunction "D7/SCL/MISO/TX_31") (pintype "bidirectional"))
    )
    (net (code "8") (name "/NFC_SDA") (class "Default")
      (node (ref "R19") (pin "2") (pinfunction "2_2") (pintype "passive"))
      (node (ref "TP17") (pin "1") (pinfunction "1_1") (pintype "passive"))
      (node (ref "U6") (pin "27") (pinfunction "IO33/SDA_27") (pintype "bidirectional"))
      (node (ref "U7") (pin "24") (pinfunction "SDA/~{SS}/RX_24") (pintype "bidirectional"))
    )
    (net (code "9") (name "/NFC_~{IRQ}") (class "Default")
      (node (ref "R19") (pin "3") (pinfunction "3_3") (pintype "passive"))
      (node (ref "TP16") (pin "1") (pinfunction "1_1") (pintype "passive"))
      (node (ref "U6") (pin "25") (pinfunction "IO26_25") (pintype "bidirectional"))
      (node (ref "U7") (pin "23") (pinfunction "IRQ_23") (pintype "output"))
    )
    (net (code "10") (name "/NFC_~{RST}") (class "Default")
      (node (ref "R19") (pin "4") (pinfunction "4_4") (pintype "passive"))
      (node (ref "TP15") (pin "1") (pinfunction "1_1") (pintype "passive"))
      (node (ref "U6") (pin "24") (pinfunction "IO21_24") (pintype "bidirectional"))
      (node (ref "U7") (pin "6") (pinfunction "~{RSTPD}_6") (pintype "input"))
    )
    (net (code "11") (name "/PWR_BTN") (class "Default")
      (node (ref "D2") (pin "A") (pinfunction "A_A") (pintype "passive"))
      (node (ref "TP8") (pin "1") (pinfunction "1_1") (pintype "passive"))
      (node (ref "U6") (pin "5") (pinfunction "IO2_5") (pintype "bidirectional"))
    )
    (net (code "12") (name "/PWR_OFF") (class "Default")
      (node (ref "K7") (pin "G") (pinfunction "G_G") (pintype "passive"))
      (node (ref "R16") (pin "2") (pinfunction "2_2") (pintype "passive"))
      (node (ref "TP12") (pin "1") (pinfunction "1_1") (pintype "passive"))
      (node (ref "U6") (pin "4") (pinfunction "IO1_4") (pintype "bidirectional"))
    )
    (net (code "13") (name "/SYS_BZR") (class "Default")
      (node (ref "K9") (pin "G") (pinfunction "G_G") (pintype "passive"))
      (node (ref "R28") (pin "2") (pinfunction "2_2") (pintype "passive"))
      (node (ref "U6") (pin "40") (pinfunction "IO46_40") (pintype "bidirectional"))
    )
    (net (code "14") (name "/SYS_LED") (class "Default")
      (node (ref "K8") (pin "S") (pinfunction "S_S") (pintype "passive"))
      (node (ref "U6") (pin "39") (pinfunction "IO45_39") (pintype "bidirectional"))
    )
    (net (code "15") (name "/USB_D_N") (class "Default")
      (node (ref "D6") (pin "6") (pinfunction "D1-_6") (pintype "passive"))
      (node (ref "U6") (pin "22") (pinfunction "IO19/D-_22") (pintype "bidirectional"))
      (node (ref "X3") (pin "A7") (pinfunction "DN1_A7") (pintype "passive"))
      (node (ref "X3") (pin "B7") (pinfunction "DN2_B7") (pintype "passive"))
    )
    (net (code "16") (name "/USB_D_P") (class "Default")
      (node (ref "D6") (pin "1") (pinfunction "D1+_1") (pintype "passive"))
      (node (ref "U6") (pin "23") (pinfunction "IO20/D+_23") (pintype "bidirectional"))
      (node (ref "X3") (pin "A6") (pinfunction "DP1_A6") (pintype "passive"))
      (node (ref "X3") (pin "B6") (pinfunction "DP2_B6") (pintype "passive"))
    )
    (net (code "17") (name "/~{RST}") (class "Default")
      (node (ref "C33") (pin "2") (pinfunction "2_2") (pintype "passive"))
      (node (ref "R21") (pin "1") (pinfunction "1_1") (pintype "passive"))
      (node (ref "S2") (pin "1") (pinfunction "1_1") (pintype "passive"))
      (node (ref "U6") (pin "41") (pinfunction "EN_41") (pintype "input"))
    )
    (net (code "18") (name "3V3") (class "Default")
      (node (ref "C1") (pin "1") (pinfunction "1_1") (pintype "passive"))
      (node (ref "C19") (pin "P") (pinfunction "+_P") (pintype "passive"))
      (node (ref "C20") (pin "2") (pinfunction "2_2") (pintype "passive"))
      (node (ref "C21") (pin "2") (pinfunction "2_2") (pintype "passive"))
      (node (ref "C22") (pin "2") (pinfunction "2_2") (pintype "passive"))
      (node (ref "C23") (pin "2") (pinfunction "2_2") (pintype "passive"))
      (node (ref "C3") (pin "2") (pinfunction "2_2") (pintype "passive"))
      (node (ref "C37") (pin "2") (pinfunction "2_2") (pintype "passive"))
      (node (ref "C38") (pin "2") (pinfunction "2_2") (pintype "passive"))
      (node (ref "C39") (pin "2") (pinfunction "2_2") (pintype "passive"))
      (node (ref "C4") (pin "P") (pinfunction "+_P") (pintype "passive"))
      (node (ref "C5") (pin "2") (pinfunction "2_2") (pintype "passive"))
      (node (ref "D7") (pin "K") (pinfunction "K_K") (pintype "passive"))
      (node (ref "K8") (pin "G") (pinfunction "G_G") (pintype "passive"))
      (node (ref "L1") (pin "1") (pinfunction "1_1") (pintype "passive"))
      (node (ref "L2") (pin "2") (pinfunction "2_2") (pintype "passive"))
      (node (ref "Q2") (pin "1") (pinfunction "P_1") (pintype "power_in"))
      (node (ref "R19") (pin "5") (pinfunction "5_5") (pintype "passive"))
      (node (ref "R19") (pin "6") (pinfunction "6_6") (pintype "passive"))
      (node (ref "R19") (pin "7") (pinfunction "7_7") (pintype "passive"))
      (node (ref "R19") (pin "8") (pinfunction "8_8") (pintype "passive"))
      (node (ref "R21") (pin "2") (pinfunction "2_2") (pintype "passive"))
      (node (ref "R22") (pin "2") (pinfunction "2_2") (pintype "passive"))
      (node (ref "R3") (pin "2") (pinfunction "2_2") (pintype "passive"))
      (node (ref "TP1") (pin "1") (pinfunction "1_1") (pintype "passive"))
      (node (ref "U2") (pin "4") (pinfunction "EN_4") (pintype "input"))
      (node (ref "U2") (pin "5") (pinfunction "VIN_5") (pintype "power_in"))
      (node (ref "U6") (pin "2") (pinfunction "VCC_2") (pintype "passive"))
      (node (ref "U7") (pin "1") (pinfunction "I2C_1") (pintype "input"))
      (node (ref "U7") (pin "12") (pinfunction "TVDD_12") (pintype "power_in"))
      (node (ref "U7") (pin "15") (pinfunction "AVDD_15") (pintype "power_in"))
      (node (ref "U7") (pin "2") (pinfunction "PVDD_2") (pintype "power_in"))
      (node (ref "U7") (pin "3") (pinfunction "DVDD_3") (pintype "power_in"))
      (node (ref "U7") (pin "9") (pinfunction "SVDD_9") (pintype "power_in"))
      (node (ref "X4") (pin "6") (pinfunction "6_6") (pintype "passive"))
    )
    (net (code "19") (name "5V") (class "Default")
      (node (ref "C2") (pin "1") (pinfunction "1_1") (pintype "passive"))
      (node (ref "C40") (pin "2") (pinfunction "2_2") (pintype "passive"))
      (node (ref "C41") (pin "2") (pinfunction "2_2") (pintype "passive"))
      (node (ref "C42") (pin "2") (pinfunction "2_2") (pintype "passive"))
      (node (ref "C43") (pin "2") (pinfunction "2_2") (pintype "passive"))
      (node (ref "C44") (pin "2") (pinfunction "2_2") (pintype "passive"))
      (node (ref "C45") (pin "2") (pinfunction "2_2") (pintype "passive"))
      (node (ref "C46") (pin "2") (pinfunction "2_2") (pintype "passive"))
      (node (ref "C47") (pin "2") (pinfunction "2_2") (pintype "passive"))
      (node (ref "C48") (pin "2") (pinfunction "2_2") (pintype "passive"))
      (node (ref "C49") (pin "2") (pinfunction "2_2") (pintype "passive"))
      (node (ref "C50") (pin "2") (pinfunction "2_2") (pintype "passive"))
      (node (ref "C51") (pin "2") (pinfunction "2_2") (pintype "passive"))
      (node (ref "C52") (pin "2") (pinfunction "2_2") (pintype "passive"))
      (node (ref "C53") (pin "2") (pinfunction "2_2") (pintype "passive"))
      (node (ref "C6") (pin "P") (pinfunction "+_P") (pintype "passive"))
      (node (ref "D1") (pin "K") (pinfunction "K_K") (pintype "passive"))
      (node (ref "P10") (pin "2") (pinfunction "VCC_2") (pintype "power_in"))
      (node (ref "P11") (pin "2") (pinfunction "VCC_2") (pintype "power_in"))
      (node (ref "P12") (pin "2") (pinfunction "VCC_2") (pintype "power_in"))
      (node (ref "P13") (pin "2") (pinfunction "VCC_2") (pintype "power_in"))
      (node (ref "P14") (pin "2") (pinfunction "VCC_2") (pintype "power_in"))
      (node (ref "P15") (pin "2") (pinfunction "VCC_2") (pintype "power_in"))
      (node (ref "P2") (pin "3") (pinfunction "VCC_3") (pintype "power_in"))
      (node (ref "P3") (pin "3") (pinfunction "VCC_3") (pintype "power_in"))
      (node (ref "P4") (pin "3") (pinfunction "VCC_3") (pintype "power_in"))
      (node (ref "P5") (pin "3") (pinfunction "VCC_3") (pintype "power_in"))
      (node (ref "P6") (pin "2") (pinfunction "VCC_2") (pintype "power_in"))
      (node (ref "P7") (pin "2") (pinfunction "VCC_2") (pintype "power_in"))
      (node (ref "P8") (pin "2") (pinfunction "VCC_2") (pintype "power_in"))
      (node (ref "P9") (pin "2") (pinfunction "VCC_2") (pintype "power_in"))
      (node (ref "R27") (pin "2") (pinfunction "2_2") (pintype "passive"))
      (node (ref "R4") (pin "2") (pinfunction "2_2") (pintype "passive"))
      (node (ref "TP2") (pin "1") (pinfunction "1_1") (pintype "passive"))
    )
    (net (code "20") (name "GND") (class "Default")
      (node (ref "A1") (pin "3") (pinfunction "M_3") (pintype "passive"))
      (node (ref "C10") (pin "1") (pinfunction "1_1") (pintype "passive"))
      (node (ref "C11") (pin "1") (pinfunction "1_1") (pintype "passive"))
      (node (ref "C13") (pin "1") (pinfunction "1_1") (pintype "passive"))
      (node (ref "C14") (pin "1") (pinfunction "1_1") (pintype "passive"))
      (node (ref "C15") (pin "1") (pinfunction "1_1") (pintype "passive"))
      (node (ref "C17") (pin "1") (pinfunction "1_1") (pintype "passive"))
      (node (ref "C18") (pin "M") (pinfunction "-_M") (pintype "passive"))
      (node (ref "C19") (pin "M") (pinfunction "-_M") (pintype "passive"))
      (node (ref "C20") (pin "1") (pinfunction "1_1") (pintype "passive"))
      (node (ref "C21") (pin "1") (pinfunction "1_1") (pintype "passive"))
      (node (ref "C22") (pin "1") (pinfunction "1_1") (pintype "passive"))
      (node (ref "C23") (pin "1") (pinfunction "1_1") (pintype "passive"))
      (node (ref "C25") (pin "2") (pinfunction "2_2") (pintype "passive"))
      (node (ref "C26") (pin "2") (pinfunction "2_2") (pintype "passive"))
      (node (ref "C27") (pin "2") (pinfunction "2_2") (pintype "passive"))
      (node (ref "C28") (pin "1") (pinfunction "1_1") (pintype "passive"))
      (node (ref "C29") (pin "1") (pinfunction "1_1") (pintype "passive"))
      (node (ref "C3") (pin "1") (pinfunction "1_1") (pintype "passive"))
      (node (ref "C30") (pin "1") (pinfunction "1_1") (pintype "passive"))
      (node (ref "C33") (pin "1") (pinfunction "1_1") (pintype "passive"))
      (node (ref "C34") (pin "1") (pinfunction "1_1") (pintype "passive"))
      (node (ref "C35") (pin "2") (pinfunction "2_2") (pintype "passive"))
      (node (ref "C36") (pin "2") (pinfunction "2_2") (pintype "passive"))
      (node (ref "C37") (pin "1") (pinfunction "1_1") (pintype "passive"))
      (node (ref "C38") (pin "1") (pinfunction "1_1") (pintype "passive"))
      (node (ref "C39") (pin "1") (pinfunction "1_1") (pintype "passive"))
      (node (ref "C4") (pin "M") (pinfunction "-_M") (pintype "passive"))
      (node (ref "C40") (pin "1") (pinfunction "1_1") (pintype "passive"))
      (node (ref "C41") (pin "1") (pinfunction "1_1") (pintype "passive"))
      (node (ref "C42") (pin "1") (pinfunction "1_1") (pintype "passive"))
      (node (ref "C43") (pin "1") (pinfunction "1_1") (pintype "passive"))
      (node (ref "C44") (pin "1") (pinfunction "1_1") (pintype "passive"))
      (node (ref "C45") (pin "1") (pinfunction "1_1") (pintype "passive"))
      (node (ref "C46") (pin "1") (pinfunction "1_1") (pintype "passive"))
      (node (ref "C47") (pin "1") (pinfunction "1_1") (pintype "passive"))
      (node (ref "C48") (pin "1") (pinfunction "1_1") (pintype "passive"))
      (node (ref "C49") (pin "1") (pinfunction "1_1") (pintype "passive"))
      (node (ref "C5") (pin "1") (pinfunction "1_1") (pintype "passive"))
      (node (ref "C50") (pin "1") (pinfunction "1_1") (pintype "passive"))
      (node (ref "C51") (pin "1") (pinfunction "1_1") (pintype "passive"))
      (node (ref "C52") (pin "1") (pinfunction "1_1") (pintype "passive"))
      (node (ref "C53") (pin "1") (pinfunction "1_1") (pintype "passive"))
      (node (ref "C6") (pin "M") (pinfunction "-_M") (pintype "passive"))
      (node (ref "C7") (pin "1") (pinfunction "1_1") (pintype "passive"))
      (node (ref "C8") (pin "1") (pinfunction "1_1") (pintype "passive"))
      (node (ref "C9") (pin "1") (pinfunction "1_1") (pintype "passive"))
      (node (ref "D6") (pin "2") (pinfunction "GND_2") (pintype "passive"))
      (node (ref "K7") (pin "S") (pinfunction "S_S") (pintype "passive"))
      (node (ref "K9") (pin "S") (pinfunction "S_S") (pintype "passive"))
      (node (ref "P10") (pin "4") (pinfunction "GND_4") (pintype "power_in"))
      (node (ref "P11") (pin "4") (pinfunction "GND_4") (pintype "power_in"))
      (node (ref "P12") (pin "4") (pinfunction "GND_4") (pintype "power_in"))
      (node (ref "P13") (pin "4") (pinfunction "GND_4") (pintype "power_in"))
      (node (ref "P14") (pin "4") (pinfunction "GND_4") (pintype "power_in"))
      (node (ref "P15") (pin "4") (pinfunction "GND_4") (pintype "power_in"))
      (node (ref "P2") (pin "1") (pinfunction "GND_1") (pintype "power_in"))
      (node (ref "P3") (pin "1") (pinfunction "GND_1") (pintype "power_in"))
      (node (ref "P4") (pin "1") (pinfunction "GND_1") (pintype "power_in"))
      (node (ref "P5") (pin "1") (pinfunction "GND_1") (pintype "power_in"))
      (node (ref "P6") (pin "4") (pinfunction "GND_4") (pintype "power_in"))
      (node (ref "P7") (pin "4") (pinfunction "GND_4") (pintype "power_in"))
      (node (ref "P8") (pin "4") (pinfunction "GND_4") (pintype "power_in"))
      (node (ref "P9") (pin "4") (pinfunction "GND_4") (pintype "power_in"))
      (node (ref "Q1") (pin "3") (pinfunction "3_3") (pintype "passive"))
      (node (ref "R13") (pin "1") (pinfunction "1_1") (pintype "passive"))
      (node (ref "R16") (pin "1") (pinfunction "1_1") (pintype "passive"))
      (node (ref "R17") (pin "1") (pinfunction "1_1") (pintype "passive"))
      (node (ref "R18") (pin "1") (pinfunction "1_1") (pintype "passive"))
      (node (ref "R24") (pin "2") (pinfunction "2_2") (pintype "passive"))
      (node (ref "R25") (pin "2") (pinfunction "2_2") (pintype "passive"))
      (node (ref "R28") (pin "1") (pinfunction "1_1") (pintype "passive"))
      (node (ref "R5") (pin "1") (pinfunction "1_1") (pintype "passive"))
      (node (ref "R6") (pin "2") (pinfunction "2_2") (pintype "passive"))
      (node (ref "R7") (pin "1") (pinfunction "1_1") (pintype "passive"))
      (node (ref "S1") (pin "2") (pinfunction "COMMON1_2") (pintype "passive"))
      (node (ref "S2") (pin "2") (pinfunction "2_2") (pintype "passive"))
      (node (ref "S3") (pin "2") (pinfunction "2_2") (pintype "passive"))
      (node (ref "TP6") (pin "1") (pinfunction "1_1") (pintype "passive"))
      (node (ref "U1") (pin "2") (pinfunction "GND_2") (pintype "power_in"))
      (node (ref "U2") (pin "2") (pinfunction "GND_2") (pintype "power_in"))
      (node (ref "U3") (pin "1") (pinfunction "CK_1") (pintype "input"))
      (node (ref "U3") (pin "2") (pinfunction "D_2") (pintype "input"))
      (node (ref "U3") (pin "4") (pinfunction "GND_4") (pintype "power_in"))
      (node (ref "U4") (pin "2") (pinfunction "GND_2") (pintype "power_in"))
      (node (ref "U5") (pin "1") (pinfunction "VM_1") (pintype "power_in"))
      (node (ref "U6") (pin "1") (pinfunction "GND_1") (pintype "passive"))
      (node (ref "U6") (pin "26") (pinfunction "GND_26") (pintype "passive"))
      (node (ref "U6") (pin "42") (pinfunction "GND_42") (pintype "passive"))
      (node (ref "U6") (pin "43") (pinfunction "PAD_43") (pintype "passive"))
      (node (ref "U7") (pin "10") (pinfunction "TVSS_10") (pintype "power_in"))
      (node (ref "U7") (pin "14") (pinfunction "TVSS_14") (pintype "power_in"))
      (node (ref "U7") (pin "18") (pinfunction "AVSS_18") (pintype "power_in"))
      (node (ref "U7") (pin "25") (pinfunction "D1/ADR5_25") (pintype "bidirectional"))
      (node (ref "U7") (pin "26") (pinfunction "D2/ADR4_26") (pintype "bidirectional"))
      (node (ref "U7") (pin "27") (pinfunction "D3/ADR3_27") (pintype "bidirectional"))
      (node (ref "U7") (pin "28") (pinfunction "D4/ADR2_28") (pintype "bidirectional"))
      (node (ref "U7") (pin "29") (pinfunction "D5/ADR1/SCK/DTRQ_29") (pintype "bidirectional"))
      (node (ref "U7") (pin "30") (pinfunction "D6/ADR0/MOSI/MX_30") (pintype "bidirectional"))
      (node (ref "U7") (pin "32") (pinfunction "EA_32") (pintype "input"))
      (node (ref "U7") (pin "4") (pinfunction "DVSS_4") (pintype "power_in"))
      (node (ref "U7") (pin "5") (pinfunction "PVSS_5") (pintype "power_in"))
      (node (ref "U7") (pin "PAD") (pinfunction "DVSS_PAD") (pintype "passive"))
      (node (ref "X1") (pin "2") (pinfunction "2_2") (pintype "passive"))
      (node (ref "X3") (pin "A1") (pinfunction "GND_A1") (pintype "passive"))
      (node (ref "X3") (pin "A12") (pinfunction "GND_A12") (pintype "passive"))
      (node (ref "X3") (pin "B1") (pinfunction "GND_B1") (pintype "passive"))
      (node (ref "X3") (pin "B12") (pinfunction "GND_B12") (pintype "passive"))
      (node (ref "X3") (pin "G1") (pinfunction "SHLD1_G1") (pintype "passive"))
      (node (ref "X3") (pin "G2") (pinfunction "SHLD2_G2") (pintype "passive"))
      (node (ref "X3") (pin "G3") (pinfunction "SHLD3_G3") (pintype "passive"))
      (node (ref "X3") (pin "G4") (pinfunction "SHLD4_G4") (pintype "passive"))
      (node (ref "X4") (pin "1") (pinfunction "1_1") (pintype "passive"))
    )
    (net (code "21") (name "Net-(A1-A)") (class "Default")
      (node (ref "A1") (pin "1") (pinfunction "A_1") (pintype "passive"))
      (node (ref "C24") (pin "2") (pinfunction "2_2") (pintype "passive"))
      (node (ref "C26") (pin "1") (pinfunction "1_1") (pintype "passive"))
      (node (ref "C27") (pin "1") (pinfunction "1_1") (pintype "passive"))
    )
    (net (code "22") (name "Net-(A1-B)") (class "Default")
      (node (ref "A1") (pin "2") (pinfunction "B_2") (pintype "passive"))
      (node (ref "C29") (pin "2") (pinfunction "2_2") (pintype "passive"))
      (node (ref "C30") (pin "2") (pinfunction "2_2") (pintype "passive"))
      (node (ref "C31") (pin "2") (pinfunction "2_2") (pintype "passive"))
      (node (ref "C32") (pin "1") (pinfunction "1_1") (pintype "passive"))
    )
    (net (code "23") (name "Net-(C24-Pad1)") (class "Default")
      (node (ref "C24") (pin "1") (pinfunction "1_1") (pintype "passive"))
      (node (ref "C25") (pin "1") (pinfunction "1_1") (pintype "passive"))
      (node (ref "L3") (pin "2") (pinfunction "2_2") (pintype "passive"))
    )
    (net (code "24") (name "Net-(C28-Pad2)") (class "Default")
      (node (ref "C28") (pin "2") (pinfunction "2_2") (pintype "passive"))
      (node (ref "C31") (pin "1") (pinfunction "1_1") (pintype "passive"))
      (node (ref "L4") (pin "2") (pinfunction "2_2") (pintype "passive"))
    )
    (net (code "25") (name "Net-(C32-Pad2)") (class "Default")
      (node (ref "C32") (pin "2") (pinfunction "2_2") (pintype "passive"))
      (node (ref "R20") (pin "2") (pinfunction "2_2") (pintype "passive"))
    )
    (net (code "26") (name "Net-(D4-PadK)") (class "Default")
      (node (ref "D4") (pin "K") (pinfunction "K_K") (pintype "passive"))
      (node (ref "K2") (pin "D") (pinfunction "D_D") (pintype "passive"))
      (node (ref "K3") (pin "G") (pinfunction "G_G") (pintype "passive"))
      (node (ref "R14") (pin "2") (pinfunction "2_2") (pintype "passive"))
      (node (ref "TP9") (pin "1") (pinfunction "1_1") (pintype "passive"))
    )
    (net (code "27") (name "Net-(D5-PadK)") (class "Default")
      (node (ref "D5") (pin "K") (pinfunction "K_K") (pintype "passive"))
      (node (ref "K4") (pin "D") (pinfunction "D_D") (pintype "passive"))
      (node (ref "K5") (pin "G") (pinfunction "G_G") (pintype "passive"))
      (node (ref "R15") (pin "2") (pinfunction "2_2") (pintype "passive"))
      (node (ref "TP10") (pin "1") (pinfunction "1_1") (pintype "passive"))
    )
    (net (code "28") (name "Net-(K1-PadD)") (class "Default")
      (node (ref "K1") (pin "D") (pinfunction "D_D") (pintype "passive"))
      (node (ref "R11") (pin "2") (pinfunction "2_2") (pintype "passive"))
    )
    (net (code "29") (name "Net-(K9-PadD)") (class "Default")
      (node (ref "K9") (pin "D") (pinfunction "D_D") (pintype "passive"))
      (node (ref "R26") (pin "2") (pinfunction "2_2") (pintype "passive"))
    )
    (net (code "30") (name "Net-(P1-PadK)") (class "Default")
      (node (ref "P1") (pin "K") (pinfunction "K_K") (pintype "passive"))
      (node (ref "R12") (pin "1") (pinfunction "1_1") (pintype "passive"))
    )
    (net (code "31") (name "Net-(P2-IN)") (class "Default")
      (node (ref "K8") (pin "D") (pinfunction "D_D") (pintype "passive"))
      (node (ref "P2") (pin "2") (pinfunction "IN_2") (pintype "power_in"))
      (node (ref "R27") (pin "1") (pinfunction "1_1") (pintype "passive"))
    )
    (net (code "32") (name "Net-(P2-OUT)") (class "Default")
      (node (ref "P2") (pin "4") (pinfunction "OUT_4") (pintype "power_in"))
      (node (ref "P3") (pin "2") (pinfunction "IN_2") (pintype "power_in"))
    )
    (net (code "33") (name "Net-(P3-OUT)") (class "Default")
      (node (ref "P3") (pin "4") (pinfunction "OUT_4") (pintype "power_in"))
      (node (ref "P4") (pin "2") (pinfunction "IN_2") (pintype "power_in"))
    )
    (net (code "34") (name "Net-(P4-OUT)") (class "Default")
      (node (ref "P4") (pin "4") (pinfunction "OUT_4") (pintype "power_in"))
      (node (ref "P5") (pin "2") (pinfunction "IN_2") (pintype "power_in"))
    )
    (net (code "35") (name "Net-(P5-OUT)") (class "Default")
      (node (ref "P5") (pin "4") (pinfunction "OUT_4") (pintype "power_in"))
      (node (ref "P6") (pin "1") (pinfunction "IN_1") (pintype "power_in"))
    )
    (net (code "36") (name "Net-(P6-OUT)") (class "Default")
      (node (ref "P6") (pin "3") (pinfunction "OUT_3") (pintype "power_in"))
      (node (ref "P7") (pin "1") (pinfunction "IN_1") (pintype "power_in"))
    )
    (net (code "37") (name "Net-(P7-OUT)") (class "Default")
      (node (ref "P7") (pin "3") (pinfunction "OUT_3") (pintype "power_in"))
      (node (ref "P8") (pin "1") (pinfunction "IN_1") (pintype "power_in"))
    )
    (net (code "38") (name "Net-(P8-OUT)") (class "Default")
      (node (ref "P8") (pin "3") (pinfunction "OUT_3") (pintype "power_in"))
      (node (ref "P9") (pin "1") (pinfunction "IN_1") (pintype "power_in"))
    )
    (net (code "39") (name "Net-(P10-IN)") (class "Default")
      (node (ref "P10") (pin "1") (pinfunction "IN_1") (pintype "power_in"))
      (node (ref "P9") (pin "3") (pinfunction "OUT_3") (pintype "power_in"))
    )
    (net (code "40") (name "Net-(P10-OUT)") (class "Default")
      (node (ref "P10") (pin "3") (pinfunction "OUT_3") (pintype "power_in"))
      (node (ref "P11") (pin "1") (pinfunction "IN_1") (pintype "power_in"))
    )
    (net (code "41") (name "Net-(P11-OUT)") (class "Default")
      (node (ref "P11") (pin "3") (pinfunction "OUT_3") (pintype "power_in"))
      (node (ref "P12") (pin "1") (pinfunction "IN_1") (pintype "power_in"))
    )
    (net (code "42") (name "Net-(P12-OUT)") (class "Default")
      (node (ref "P12") (pin "3") (pinfunction "OUT_3") (pintype "power_in"))
      (node (ref "P13") (pin "1") (pinfunction "IN_1") (pintype "power_in"))
    )
    (net (code "43") (name "Net-(P13-OUT)") (class "Default")
      (node (ref "P13") (pin "3") (pinfunction "OUT_3") (pintype "power_in"))
      (node (ref "P14") (pin "1") (pinfunction "IN_1") (pintype "power_in"))
    )
    (net (code "44") (name "Net-(P14-OUT)") (class "Default")
      (node (ref "P14") (pin "3") (pinfunction "OUT_3") (pintype "power_in"))
      (node (ref "P15") (pin "1") (pinfunction "IN_1") (pintype "power_in"))
    )
    (net (code "45") (name "Net-(Q2-M)") (class "Default")
      (node (ref "D7") (pin "A") (pinfunction "A_A") (pintype "passive"))
      (node (ref "Q2") (pin "2") (pinfunction "M_2") (pintype "power_in"))
      (node (ref "R26") (pin "1") (pinfunction "1_1") (pintype "passive"))
    )
    (net (code "46") (name "Net-(S1-NO1)") (class "Default")
      (node (ref "C13") (pin "2") (pinfunction "2_2") (pintype "passive"))
      (node (ref "D2") (pin "K") (pinfunction "K_K") (pintype "passive"))
      (node (ref "R1") (pin "1") (pinfunction "1_1") (pintype "passive"))
      (node (ref "S1") (pin "3") (pinfunction "NO1_3") (pintype "passive"))
      (node (ref "U3") (pin "7") (pinfunction "~{PR}_7") (pintype "input"))
      (node (ref "X1") (pin "1") (pinfunction "1_1") (pintype "passive"))
    )
    (net (code "47") (name "Net-(U1-RUN)") (class "Default")
      (node (ref "TP3") (pin "1") (pinfunction "1_1") (pintype "passive"))
      (node (ref "U1") (pin "1") (pinfunction "RUN_1") (pintype "input"))
      (node (ref "U3") (pin "5") (pinfunction "Q_5") (pintype "output"))
    )
    (net (code "48") (name "Net-(U1-SW)") (class "Default")
      (node (ref "L2") (pin "1") (pinfunction "1_1") (pintype "passive"))
      (node (ref "U1") (pin "3") (pinfunction "SW_3") (pintype "passive"))
    )
    (net (code "49") (name "Net-(U1-VFB)") (class "Default")
      (node (ref "C1") (pin "2") (pinfunction "2_2") (pintype "passive"))
      (node (ref "R3") (pin "1") (pinfunction "1_1") (pintype "passive"))
      (node (ref "R5") (pin "2") (pinfunction "2_2") (pintype "passive"))
      (node (ref "TP4") (pin "1") (pinfunction "1_1") (pintype "passive"))
      (node (ref "U1") (pin "5") (pinfunction "VFB_5") (pintype "passive"))
    )
    (net (code "50") (name "Net-(U2-FB)") (class "Default")
      (node (ref "C2") (pin "2") (pinfunction "2_2") (pintype "passive"))
      (node (ref "R4") (pin "1") (pinfunction "1_1") (pintype "passive"))
      (node (ref "R7") (pin "2") (pinfunction "2_2") (pintype "passive"))
      (node (ref "TP5") (pin "1") (pinfunction "1_1") (pintype "passive"))
      (node (ref "U2") (pin "3") (pinfunction "FB_3") (pintype "passive"))
    )
    (net (code "51") (name "Net-(U2-OC)") (class "Default")
      (node (ref "R6") (pin "1") (pinfunction "1_1") (pintype "passive"))
      (node (ref "U2") (pin "6") (pinfunction "OC_6") (pintype "passive"))
    )
    (net (code "52") (name "Net-(U2-SW)") (class "Default")
      (node (ref "D1") (pin "A") (pinfunction "A_A") (pintype "passive"))
      (node (ref "L1") (pin "2") (pinfunction "2_2") (pintype "passive"))
      (node (ref "U2") (pin "1") (pinfunction "SW_1") (pintype "passive"))
    )
    (net (code "53") (name "Net-(U3-~{CLR})") (class "Default")
      (node (ref "C14") (pin "2") (pinfunction "2_2") (pintype "passive"))
      (node (ref "K7") (pin "D") (pinfunction "D_D") (pintype "passive"))
      (node (ref "R2") (pin "1") (pinfunction "1_1") (pintype "passive"))
      (node (ref "U3") (pin "6") (pinfunction "~{CLR}_6") (pintype "input"))
    )
    (net (code "54") (name "Net-(U3-~{Q})") (class "Default")
      (node (ref "K1") (pin "G") (pinfunction "G_G") (pintype "passive"))
      (node (ref "U3") (pin "3") (pinfunction "~{Q}_3") (pintype "output"))
    )
    (net (code "55") (name "Net-(U4-PROG)") (class "Default")
      (node (ref "R13") (pin "2") (pinfunction "2_2") (pintype "passive"))
      (node (ref "U4") (pin "5") (pinfunction "PROG_5") (pintype "passive"))
    )
    (net (code "56") (name "Net-(U4-~{CHRG})") (class "Default")
      (node (ref "R12") (pin "2") (pinfunction "2_2") (pintype "passive"))
      (node (ref "U4") (pin "1") (pinfunction "~{CHRG}_1") (pintype "open_collector"))
    )
    (net (code "57") (name "Net-(U5-GND)") (class "Default")
      (node (ref "C12") (pin "1") (pinfunction "1_1") (pintype "passive"))
      (node (ref "C16") (pin "1") (pinfunction "1_1") (pintype "passive"))
      (node (ref "D4") (pin "A") (pinfunction "A_A") (pintype "passive"))
      (node (ref "D5") (pin "A") (pinfunction "A_A") (pintype "passive"))
      (node (ref "R14") (pin "1") (pinfunction "1_1") (pintype "passive"))
      (node (ref "R15") (pin "1") (pinfunction "1_1") (pintype "passive"))
      (node (ref "TP14") (pin "1") (pinfunction "1_1") (pintype "passive"))
      (node (ref "U5") (pin "3") (pinfunction "GND_3") (pintype "power_in"))
      (node (ref "X2") (pin "2") (pinfunction "B1N_2") (pintype "passive"))
      (node (ref "X2") (pin "4") (pinfunction "B2N_4") (pintype "passive"))
    )
    (net (code "58") (name "Net-(U5-VDD)") (class "Default")
      (node (ref "C16") (pin "2") (pinfunction "2_2") (pintype "passive"))
      (node (ref "R8") (pin "1") (pinfunction "1_1") (pintype "passive"))
      (node (ref "U5") (pin "2") (pinfunction "VDD_2") (pintype "power_in"))
    )
    (net (code "59") (name "Net-(U7-OSCIN)") (class "Default")
      (node (ref "C36") (pin "1") (pinfunction "1_1") (pintype "passive"))
      (node (ref "Q1") (pin "2") (pinfunction "2_2") (pintype "passive"))
      (node (ref "U7") (pin "21") (pinfunction "OSCIN_21") (pintype "passive"))
    )
    (net (code "60") (name "Net-(U7-OSCOUT)") (class "Default")
      (node (ref "C35") (pin "1") (pinfunction "1_1") (pintype "passive"))
      (node (ref "Q1") (pin "1") (pinfunction "1_1") (pintype "passive"))
      (node (ref "U7") (pin "22") (pinfunction "OSCOUT_22") (pintype "passive"))
    )
    (net (code "61") (name "Net-(U7-RX)") (class "Default")
      (node (ref "R20") (pin "1") (pinfunction "1_1") (pintype "passive"))
      (node (ref "R23") (pin "1") (pinfunction "1_1") (pintype "passive"))
      (node (ref "U7") (pin "17") (pinfunction "RX_17") (pintype "passive"))
    )
    (net (code "62") (name "Net-(U7-TX1)") (class "Default")
      (node (ref "L3") (pin "1") (pinfunction "1_1") (pintype "passive"))
      (node (ref "U7") (pin "11") (pinfunction "TX1_11") (pintype "passive"))
    )
    (net (code "63") (name "Net-(U7-TX2)") (class "Default")
      (node (ref "L4") (pin "1") (pinfunction "1_1") (pintype "passive"))
      (node (ref "U7") (pin "13") (pinfunction "TX2_13") (pintype "passive"))
    )
    (net (code "64") (name "Net-(U7-VMID)") (class "Default")
      (node (ref "C34") (pin "2") (pinfunction "2_2") (pintype "passive"))
      (node (ref "R23") (pin "2") (pinfunction "2_2") (pintype "passive"))
      (node (ref "TP19") (pin "1") (pinfunction "1_1") (pintype "passive"))
      (node (ref "U7") (pin "16") (pinfunction "VMID_16") (pintype "passive"))
    )
    (net (code "65") (name "Net-(X2A-B1P)") (class "Default")
      (node (ref "K2") (pin "G") (pinfunction "G_G") (pintype "passive"))
      (node (ref "K3") (pin "D") (pinfunction "D_D") (pintype "passive"))
      (node (ref "R9") (pin "1") (pinfunction "1_1") (pintype "passive"))
      (node (ref "X2") (pin "1") (pinfunction "B1P_1") (pintype "passive"))
    )
    (net (code "66") (name "Net-(X2B-B2P)") (class "Default")
      (node (ref "K4") (pin "G") (pinfunction "G_G") (pintype "passive"))
      (node (ref "K5") (pin "D") (pinfunction "D_D") (pintype "passive"))
      (node (ref "R10") (pin "1") (pinfunction "1_1") (pintype "passive"))
      (node (ref "X2") (pin "3") (pinfunction "B2P_3") (pintype "passive"))
    )
    (net (code "67") (name "Net-(X3-CC1)") (class "Default")
      (node (ref "R25") (pin "1") (pinfunction "1_1") (pintype "passive"))
      (node (ref "X3") (pin "A5") (pinfunction "CC1_A5") (pintype "passive"))
    )
    (net (code "68") (name "Net-(X3-CC2)") (class "Default")
      (node (ref "R24") (pin "1") (pinfunction "1_1") (pintype "passive"))
      (node (ref "X3") (pin "B5") (pinfunction "CC2_B5") (pintype "passive"))
    )
    (net (code "69") (name "VBAT") (class "Default")
      (node (ref "C10") (pin "2") (pinfunction "2_2") (pintype "passive"))
      (node (ref "C11") (pin "2") (pinfunction "2_2") (pintype "passive"))
      (node (ref "C12") (pin "2") (pinfunction "2_2") (pintype "passive"))
      (node (ref "K1") (pin "S") (pinfunction "S_S") (pintype "passive"))
      (node (ref "K2") (pin "S") (pinfunction "S_S") (pintype "passive"))
      (node (ref "K3") (pin "S") (pinfunction "S_S") (pintype "passive"))
      (node (ref "K4") (pin "S") (pinfunction "S_S") (pintype "passive"))
      (node (ref "K5") (pin "S") (pinfunction "S_S") (pintype "passive"))
      (node (ref "K6") (pin "D") (pinfunction "D_D") (pintype "passive"))
      (node (ref "R10") (pin "2") (pinfunction "2_2") (pintype "passive"))
      (node (ref "R8") (pin "2") (pinfunction "2_2") (pintype "passive"))
      (node (ref "R9") (pin "2") (pinfunction "2_2") (pintype "passive"))
      (node (ref "TP7") (pin "1") (pinfunction "1_1") (pintype "passive"))
      (node (ref "U4") (pin "3") (pinfunction "BAT_3") (pintype "passive"))
    )
    (net (code "70") (name "VBUS") (class "Default")
      (node (ref "C9") (pin "2") (pinfunction "2_2") (pintype "passive"))
      (node (ref "D3") (pin "A") (pinfunction "A_A") (pintype "passive"))
      (node (ref "K6") (pin "G") (pinfunction "G_G") (pintype "passive"))
      (node (ref "P1") (pin "A") (pinfunction "A_A") (pintype "passive"))
      (node (ref "R18") (pin "2") (pinfunction "2_2") (pintype "passive"))
      (node (ref "U4") (pin "4") (pinfunction "VCC_4") (pintype "power_in"))
      (node (ref "X3") (pin "A4") (pinfunction "VBUS_A4") (pintype "passive"))
      (node (ref "X3") (pin "A9") (pinfunction "VBUS_A9") (pintype "passive"))
      (node (ref "X3") (pin "B4") (pinfunction "VBUS_B4") (pintype "passive"))
      (node (ref "X3") (pin "B9") (pinfunction "VBUS_B9") (pintype "passive"))
    )
    (net (code "71") (name "VIN") (class "Default")
      (node (ref "C17") (pin "2") (pinfunction "2_2") (pintype "passive"))
      (node (ref "C18") (pin "P") (pinfunction "+_P") (pintype "passive"))
      (node (ref "C7") (pin "2") (pinfunction "2_2") (pintype "passive"))
      (node (ref "C8") (pin "2") (pinfunction "2_2") (pintype "passive"))
      (node (ref "D3") (pin "K") (pinfunction "K_K") (pintype "passive"))
      (node (ref "K6") (pin "S") (pinfunction "S_S") (pintype "passive"))
      (node (ref "R1") (pin "2") (pinfunction "2_2") (pintype "passive"))
      (node (ref "R2") (pin "2") (pinfunction "2_2") (pintype "passive"))
      (node (ref "TP11") (pin "1") (pinfunction "1_1") (pintype "passive"))
      (node (ref "U1") (pin "4") (pinfunction "VIN_4") (pintype "power_in"))
      (node (ref "U3") (pin "8") (pinfunction "VCC_8") (pintype "power_in"))
    )
    (net (code "72") (name "unconnected-(D6-D2+-Pad3)") (class "Default")
      (node (ref "D6") (pin "3") (pinfunction "D2+_3") (pintype "passive+no_connect"))
    )
    (net (code "73") (name "unconnected-(D6-D2--Pad4)") (class "Default")
      (node (ref "D6") (pin "4") (pinfunction "D2-_4") (pintype "passive+no_connect"))
    )
    (net (code "74") (name "unconnected-(D6-NC-Pad5)") (class "Default")
      (node (ref "D6") (pin "5") (pinfunction "NC_5") (pintype "passive+no_connect"))
    )
    (net (code "75") (name "unconnected-(M1-Pad1)") (class "Default")
      (node (ref "M1") (pin "1") (pinfunction "1_1") (pintype "passive"))
    )
    (net (code "76") (name "unconnected-(M2-Pad1)") (class "Default")
      (node (ref "M2") (pin "1") (pinfunction "1_1") (pintype "passive"))
    )
    (net (code "77") (name "unconnected-(M3-Pad1)") (class "Default")
      (node (ref "M3") (pin "1") (pinfunction "1_1") (pintype "passive"))
    )
    (net (code "78") (name "unconnected-(M4-Pad1)") (class "Default")
      (node (ref "M4") (pin "1") (pinfunction "1_1") (pintype "passive"))
    )
    (net (code "79") (name "unconnected-(P15-OUT-Pad3)") (class "Default")
      (node (ref "P15") (pin "3") (pinfunction "OUT_3") (pintype "power_in+no_connect"))
    )
    (net (code "80") (name "unconnected-(S1-NC1-Pad1)") (class "Default")
      (node (ref "S1") (pin "1") (pinfunction "NC1_1") (pintype "passive"))
    )
    (net (code "81") (name "unconnected-(U6-IO4-Pad7)") (class "Default")
      (node (ref "U6") (pin "7") (pinfunction "IO4_7") (pintype "bidirectional+no_connect"))
    )
    (net (code "82") (name "unconnected-(U6-IO5-Pad8)") (class "Default")
      (node (ref "U6") (pin "8") (pinfunction "IO5_8") (pintype "bidirectional+no_connect"))
    )
    (net (code "83") (name "unconnected-(U6-IO6-Pad9)") (class "Default")
      (node (ref "U6") (pin "9") (pinfunction "IO6_9") (pintype "bidirectional+no_connect"))
    )
    (net (code "84") (name "unconnected-(U6-IO7-Pad10)") (class "Default")
      (node (ref "U6") (pin "10") (pinfunction "IO7_10") (pintype "bidirectional+no_connect"))
    )
    (net (code "85") (name "unconnected-(U6-IO8-Pad11)") (class "Default")
      (node (ref "U6") (pin "11") (pinfunction "IO8_11") (pintype "bidirectional+no_connect"))
    )
    (net (code "86") (name "unconnected-(U6-IO9-Pad12)") (class "Default")
      (node (ref "U6") (pin "12") (pinfunction "IO9_12") (pintype "bidirectional+no_connect"))
    )
    (net (code "87") (name "unconnected-(U6-IO10-Pad13)") (class "Default")
      (node (ref "U6") (pin "13") (pinfunction "IO10_13") (pintype "bidirectional+no_connect"))
    )
    (net (code "88") (name "unconnected-(U6-IO11-Pad14)") (class "Default")
      (node (ref "U6") (pin "14") (pinfunction "IO11_14") (pintype "bidirectional+no_connect"))
    )
    (net (code "89") (name "unconnected-(U6-IO12-Pad15)") (class "Default")
      (node (ref "U6") (pin "15") (pinfunction "IO12_15") (pintype "bidirectional+no_connect"))
    )
    (net (code "90") (name "unconnected-(U6-IO13-Pad16)") (class "Default")
      (node (ref "U6") (pin "16") (pinfunction "IO13_16") (pintype "bidirectional+no_connect"))
    )
    (net (code "91") (name "unconnected-(U6-IO14-Pad17)") (class "Default")
      (node (ref "U6") (pin "17") (pinfunction "IO14_17") (pintype "bidirectional+no_connect"))
    )
    (net (code "92") (name "unconnected-(U6-IO15-Pad18)") (class "Default")
      (node (ref "U6") (pin "18") (pinfunction "IO15_18") (pintype "bidirectional+no_connect"))
    )
    (net (code "93") (name "unconnected-(U6-IO16-Pad19)") (class "Default")
      (node (ref "U6") (pin "19") (pinfunction "IO16_19") (pintype "bidirectional+no_connect"))
    )
    (net (code "94") (name "unconnected-(U6-IO17-Pad20)") (class "Default")
      (node (ref "U6") (pin "20") (pinfunction "IO17_20") (pintype "bidirectional+no_connect"))
    )
    (net (code "95") (name "unconnected-(U6-IO18-Pad21)") (class "Default")
      (node (ref "U6") (pin "21") (pinfunction "IO18_21") (pintype "bidirectional+no_connect"))
    )
    (net (code "96") (name "unconnected-(U6-IO39{slash}TCK-Pad33)") (class "Default")
      (node (ref "U6") (pin "33") (pinfunction "IO39/TCK_33") (pintype "bidirectional+no_connect"))
    )
    (net (code "97") (name "unconnected-(U6-IO40{slash}TDO-Pad34)") (class "Default")
      (node (ref "U6") (pin "34") (pinfunction "IO40/TDO_34") (pintype "bidirectional+no_connect"))
    )
    (net (code "98") (name "unconnected-(U6-IO41{slash}TDI-Pad35)") (class "Default")
      (node (ref "U6") (pin "35") (pinfunction "IO41/TDI_35") (pintype "bidirectional+no_connect"))
    )
    (net (code "99") (name "unconnected-(U6-IO42{slash}TMS-Pad36)") (class "Default")
      (node (ref "U6") (pin "36") (pinfunction "IO42/TMS_36") (pintype "bidirectional+no_connect"))
    )
    (net (code "100") (name "unconnected-(U6-RXD-Pad38)") (class "Default")
      (node (ref "U6") (pin "38") (pinfunction "RXD_38") (pintype "input+no_connect"))
    )
    (net (code "101") (name "unconnected-(U6-TXD-Pad37)") (class "Default")
      (node (ref "U6") (pin "37") (pinfunction "TXD_37") (pintype "output+no_connect"))
    )
    (net (code "102") (name "unconnected-(U7-AUX1-Pad19)") (class "Default")
      (node (ref "U7") (pin "19") (pinfunction "AUX1_19") (pintype "passive+no_connect"))
    )
    (net (code "103") (name "unconnected-(U7-AUX2-Pad20)") (class "Default")
      (node (ref "U7") (pin "20") (pinfunction "AUX2_20") (pintype "passive+no_connect"))
    )
    (net (code "104") (name "unconnected-(U7-MFIN-Pad7)") (class "Default")
      (node (ref "U7") (pin "7") (pinfunction "MFIN_7") (pintype "input+no_connect"))
    )
    (net (code "105") (name "unconnected-(U7-MFOUT-Pad8)") (class "Default")
      (node (ref "U7") (pin "8") (pinfunction "MFOUT_8") (pintype "output+no_connect"))
    )
  )
)
